# design.net
KiCad netlist of a schematic drawn in Altium Designer
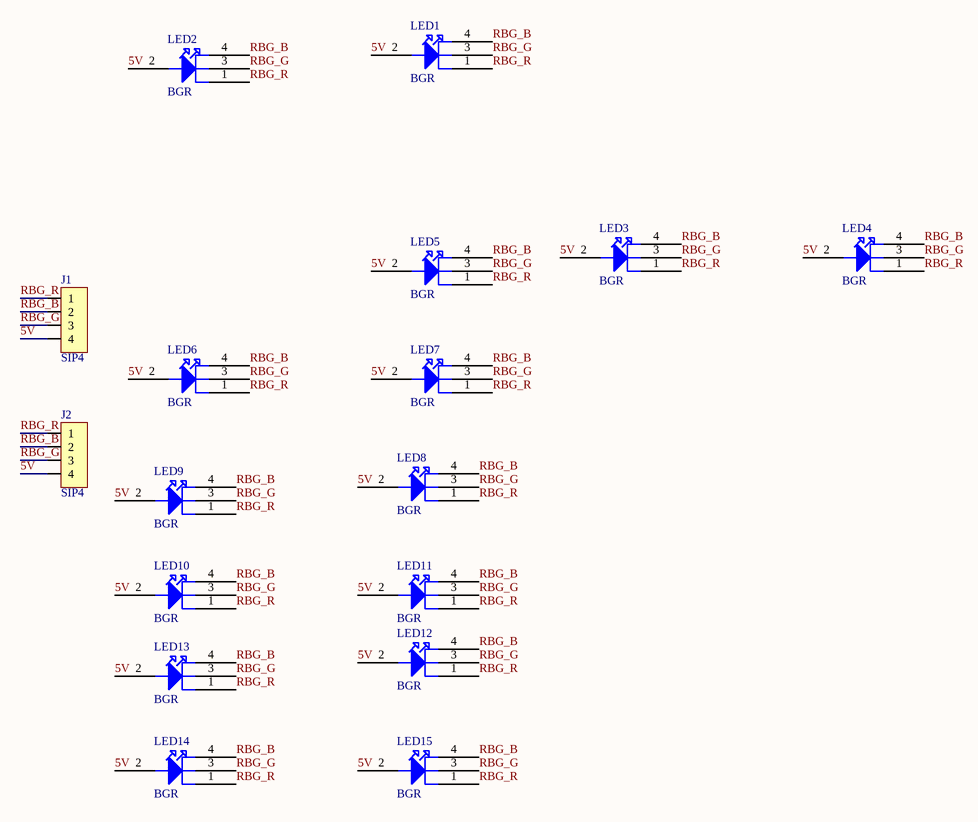
[diagram p0: 智能灯_灯泡.SchDoc]

(export (version "E")
  (design (tool "Eeschema 10.0.6"))
  (components
    (comp (ref "J1") (value "SIP4") (footprint "P4_2.54-1") (libsource (lib "狗尾巴草设计室") (part "SIP4")))
    (comp (ref "J2") (value "SIP4") (footprint "P4_2.54-1") (libsource (lib "狗尾巴草设计室") (part "SIP4")))
    (comp (ref "LED1")
      (value "BGR")
      (footprint "10mmRBG")
      (description "DUAL_LED共阳三色")
      (libsource (lib "狗尾巴草设计室") (part "LED_4P"))
    )
    (comp (ref "LED2")
      (value "BGR")
      (footprint "10mmRBG")
      (description "DUAL_LED共阳三色")
      (libsource (lib "狗尾巴草设计室") (part "LED_4P"))
    )
    (comp (ref "LED3")
      (value "BGR")
      (footprint "10mmRBG")
      (description "DUAL_LED共阳三色")
      (libsource (lib "狗尾巴草设计室") (part "LED_4P"))
    )
    (comp (ref "LED4")
      (value "BGR")
      (footprint "10mmRBG")
      (description "DUAL_LED共阳三色")
      (libsource (lib "狗尾巴草设计室") (part "LED_4P"))
    )
    (comp (ref "LED5")
      (value "BGR")
      (footprint "10mmRBG")
      (description "DUAL_LED共阳三色")
      (libsource (lib "狗尾巴草设计室") (part "LED_4P"))
    )
    (comp (ref "LED6")
      (value "BGR")
      (footprint "10mmRBG")
      (description "DUAL_LED共阳三色")
      (libsource (lib "狗尾巴草设计室") (part "LED_4P"))
    )
    (comp (ref "LED7")
      (value "BGR")
      (footprint "10mmRBG")
      (description "DUAL_LED共阳三色")
      (libsource (lib "狗尾巴草设计室") (part "LED_4P"))
    )
    (comp (ref "LED8")
      (value "BGR")
      (footprint "10mmRBG")
      (description "DUAL_LED共阳三色")
      (libsource (lib "狗尾巴草设计室") (part "LED_4P"))
    )
    (comp (ref "LED9")
      (value "BGR")
      (footprint "10mmRBG")
      (description "DUAL_LED共阳三色")
      (libsource (lib "狗尾巴草设计室") (part "LED_4P"))
    )
    (comp (ref "LED10")
      (value "BGR")
      (footprint "10mmRBG")
      (description "DUAL_LED共阳三色")
      (libsource (lib "狗尾巴草设计室") (part "LED_4P"))
    )
    (comp (ref "LED11")
      (value "BGR")
      (footprint "10mmRBG")
      (description "DUAL_LED共阳三色")
      (libsource (lib "狗尾巴草设计室") (part "LED_4P"))
    )
    (comp (ref "LED12")
      (value "BGR")
      (footprint "10mmRBG")
      (description "DUAL_LED共阳三色")
      (libsource (lib "狗尾巴草设计室") (part "LED_4P"))
    )
    (comp (ref "LED13")
      (value "BGR")
      (footprint "10mmRBG")
      (description "DUAL_LED共阳三色")
      (libsource (lib "狗尾巴草设计室") (part "LED_4P"))
    )
    (comp (ref "LED14")
      (value "BGR")
      (footprint "10mmRBG")
      (description "DUAL_LED共阳三色")
      (libsource (lib "狗尾巴草设计室") (part "LED_4P"))
    )
    (comp (ref "LED15")
      (value "BGR")
      (footprint "10mmRBG")
      (description "DUAL_LED共阳三色")
      (libsource (lib "狗尾巴草设计室") (part "LED_4P"))
    )
  )
  (nets
    (net (code "1") (name "/5V") (class "Default")
      (node (ref "J1") (pin "4") (pinfunction "4_4") (pintype "passive"))
      (node (ref "J2") (pin "4") (pinfunction "4_4") (pintype "passive"))
      (node (ref "LED1") (pin "2") (pinfunction "2_2") (pintype "passive"))
      (node (ref "LED10") (pin "2") (pinfunction "2_2") (pintype "passive"))
      (node (ref "LED11") (pin "2") (pinfunction "2_2") (pintype "passive"))
      (node (ref "LED12") (pin "2") (pinfunction "2_2") (pintype "passive"))
      (node (ref "LED13") (pin "2") (pinfunction "2_2") (pintype "passive"))
      (node (ref "LED14") (pin "2") (pinfunction "2_2") (pintype "passive"))
      (node (ref "LED15") (pin "2") (pinfunction "2_2") (pintype "passive"))
      (node (ref "LED2") (pin "2") (pinfunction "2_2") (pintype "passive"))
      (node (ref "LED3") (pin "2") (pinfunction "2_2") (pintype "passive"))
      (node (ref "LED4") (pin "2") (pinfunction "2_2") (pintype "passive"))
      (node (ref "LED5") (pin "2") (pinfunction "2_2") (pintype "passive"))
      (node (ref "LED6") (pin "2") (pinfunction "2_2") (pintype "passive"))
      (node (ref "LED7") (pin "2") (pinfunction "2_2") (pintype "passive"))
      (node (ref "LED8") (pin "2") (pinfunction "2_2") (pintype "passive"))
      (node (ref "LED9") (pin "2") (pinfunction "2_2") (pintype "passive"))
    )
    (net (code "2") (name "/RBG_B") (class "Default")
      (node (ref "J1") (pin "2") (pinfunction "2_2") (pintype "passive"))
      (node (ref "J2") (pin "2") (pinfunction "2_2") (pintype "passive"))
      (node (ref "LED1") (pin "4") (pinfunction "4_4") (pintype "passive"))
      (node (ref "LED10") (pin "4") (pinfunction "4_4") (pintype "passive"))
      (node (ref "LED11") (pin "4") (pinfunction "4_4") (pintype "passive"))
      (node (ref "LED12") (pin "4") (pinfunction "4_4") (pintype "passive"))
      (node (ref "LED13") (pin "4") (pinfunction "4_4") (pintype "passive"))
      (node (ref "LED14") (pin "4") (pinfunction "4_4") (pintype "passive"))
      (node (ref "LED15") (pin "4") (pinfunction "4_4") (pintype "passive"))
      (node (ref "LED2") (pin "4") (pinfunction "4_4") (pintype "passive"))
      (node (ref "LED3") (pin "4") (pinfunction "4_4") (pintype "passive"))
      (node (ref "LED4") (pin "4") (pinfunction "4_4") (pintype "passive"))
      (node (ref "LED5") (pin "4") (pinfunction "4_4") (pintype "passive"))
      (node (ref "LED6") (pin "4") (pinfunction "4_4") (pintype "passive"))
      (node (ref "LED7") (pin "4") (pinfunction "4_4") (pintype "passive"))
      (node (ref "LED8") (pin "4") (pinfunction "4_4") (pintype "passive"))
      (node (ref "LED9") (pin "4") (pinfunction "4_4") (pintype "passive"))
    )
    (net (code "3") (name "/RBG_G") (class "Default")
      (node (ref "J1") (pin "3") (pinfunction "3_3") (pintype "passive"))
      (node (ref "J2") (pin "3") (pinfunction "3_3") (pintype "passive"))
      (node (ref "LED1") (pin "3") (pinfunction "3_3") (pintype "passive"))
      (node (ref "LED10") (pin "3") (pinfunction "3_3") (pintype "passive"))
      (node (ref "LED11") (pin "3") (pinfunction "3_3") (pintype "passive"))
      (node (ref "LED12") (pin "3") (pinfunction "3_3") (pintype "passive"))
      (node (ref "LED13") (pin "3") (pinfunction "3_3") (pintype "passive"))
      (node (ref "LED14") (pin "3") (pinfunction "3_3") (pintype "passive"))
      (node (ref "LED15") (pin "3") (pinfunction "3_3") (pintype "passive"))
      (node (ref "LED2") (pin "3") (pinfunction "3_3") (pintype "passive"))
      (node (ref "LED3") (pin "3") (pinfunction "3_3") (pintype "passive"))
      (node (ref "LED4") (pin "3") (pinfunction "3_3") (pintype "passive"))
      (node (ref "LED5") (pin "3") (pinfunction "3_3") (pintype "passive"))
      (node (ref "LED6") (pin "3") (pinfunction "3_3") (pintype "passive"))
      (node (ref "LED7") (pin "3") (pinfunction "3_3") (pintype "passive"))
      (node (ref "LED8") (pin "3") (pinfunction "3_3") (pintype "passive"))
      (node (ref "LED9") (pin "3") (pinfunction "3_3") (pintype "passive"))
    )
    (net (code "4") (name "/RBG_R") (class "Default")
      (node (ref "J1") (pin "1") (pinfunction "1_1") (pintype "passive"))
      (node (ref "J2") (pin "1") (pinfunction "1_1") (pintype "passive"))
      (node (ref "LED1") (pin "1") (pinfunction "1_1") (pintype "passive"))
      (node (ref "LED10") (pin "1") (pinfunction "1_1") (pintype "passive"))
      (node (ref "LED11") (pin "1") (pinfunction "1_1") (pintype "passive"))
      (node (ref "LED12") (pin "1") (pinfunction "1_1") (pintype "passive"))
      (node (ref "LED13") (pin "1") (pinfunction "1_1") (pintype "passive"))
      (node (ref "LED14") (pin "1") (pinfunction "1_1") (pintype "passive"))
      (node (ref "LED15") (pin "1") (pinfunction "1_1") (pintype "passive"))
      (node (ref "LED2") (pin "1") (pinfunction "1_1") (pintype "passive"))
      (node (ref "LED3") (pin "1") (pinfunction "1_1") (pintype "passive"))
      (node (ref "LED4") (pin "1") (pinfunction "1_1") (pintype "passive"))
      (node (ref "LED5") (pin "1") (pinfunction "1_1") (pintype "passive"))
      (node (ref "LED6") (pin "1") (pinfunction "1_1") (pintype "passive"))
      (node (ref "LED7") (pin "1") (pinfunction "1_1") (pintype "passive"))
      (node (ref "LED8") (pin "1") (pinfunction "1_1") (pintype "passive"))
      (node (ref "LED9") (pin "1") (pinfunction "1_1") (pintype "passive"))
    )
  )
)
